# lipo_status.net
KiCad netlist of a schematic drawn in EAGLE
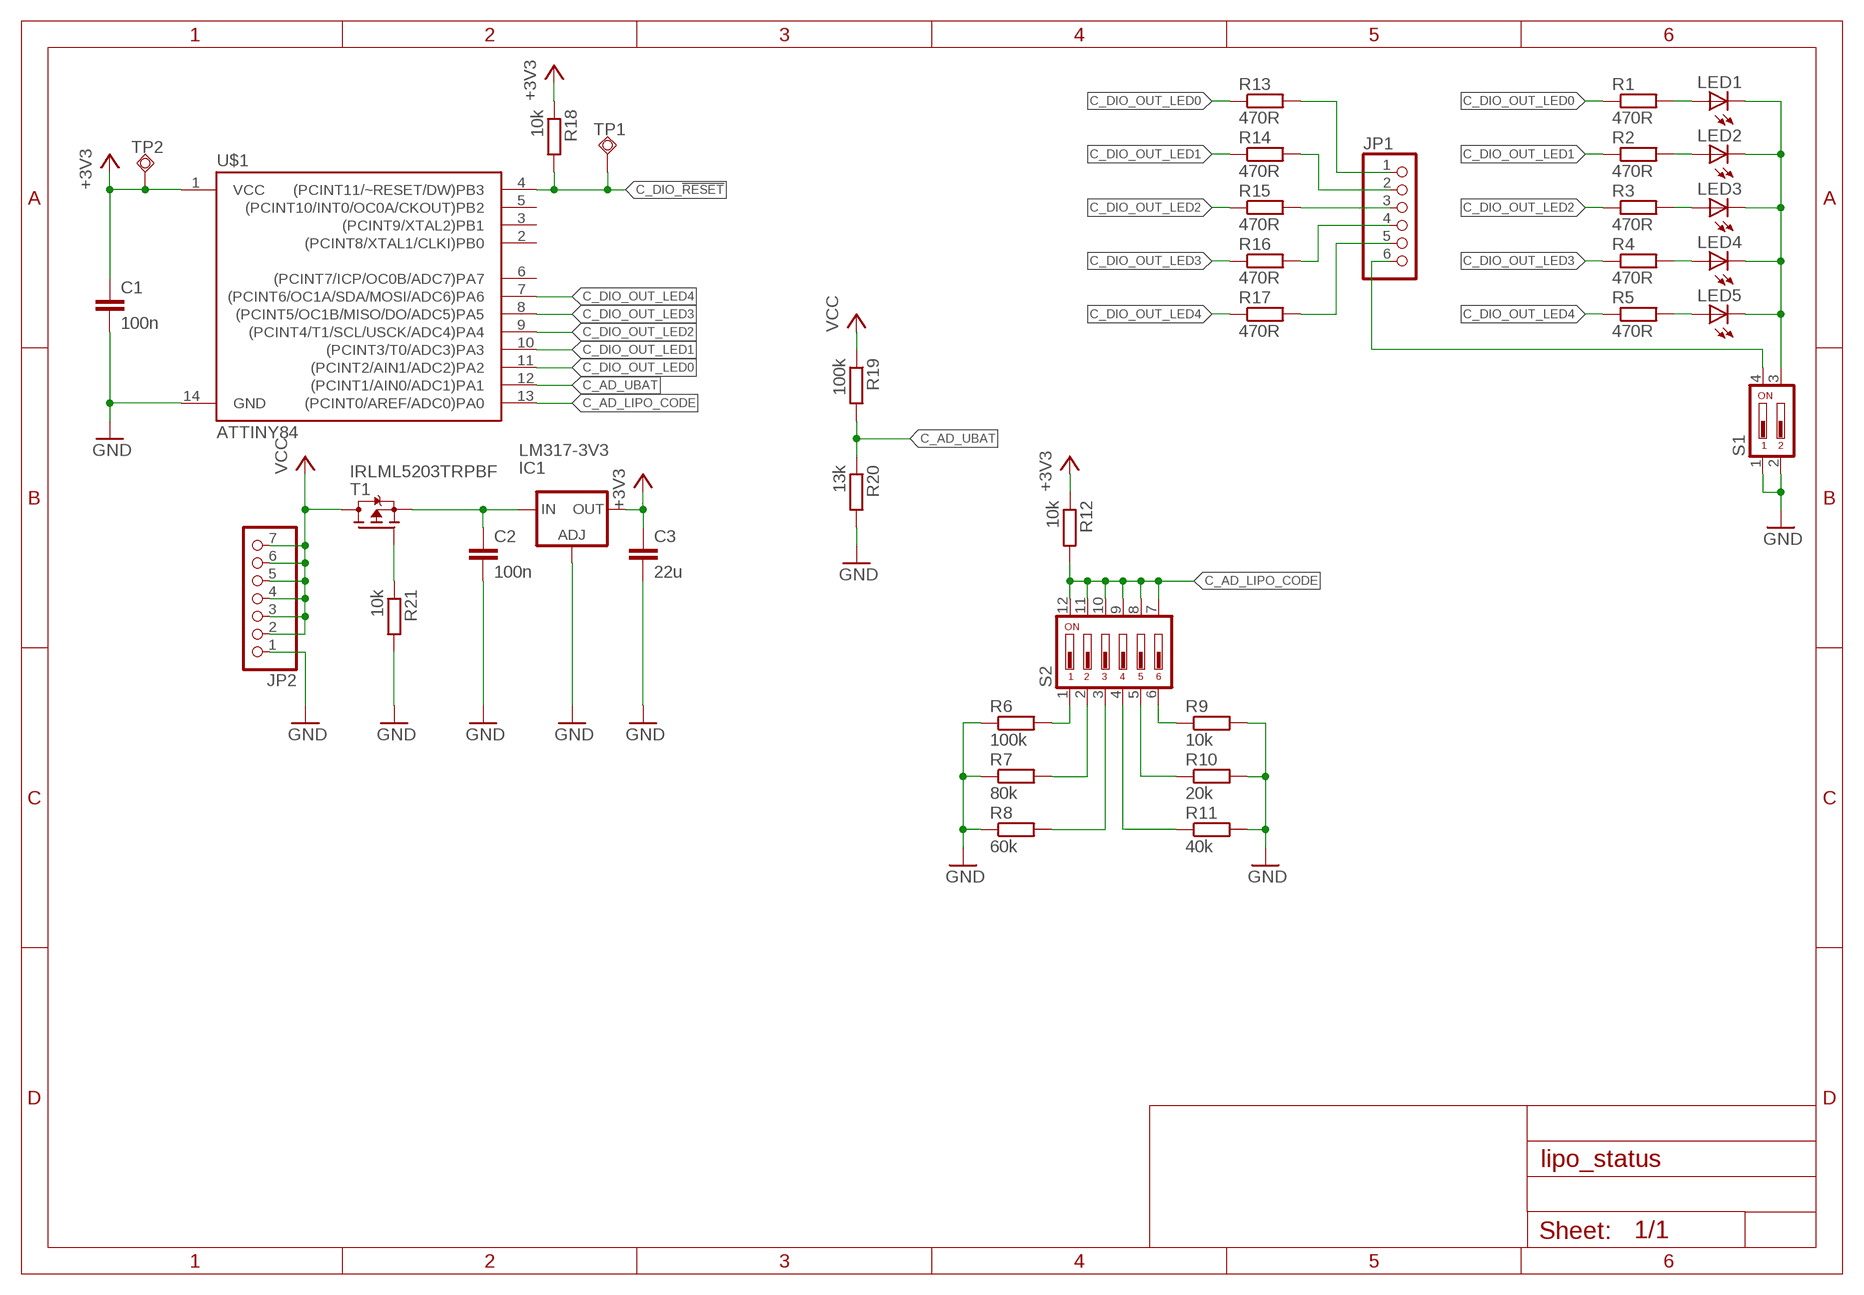
[diagram p0: schematic, sheet 1]

(export (version "E")
  (design (tool "Eeschema 10.0.6"))
  (components
    (comp (ref "C1")
      (value "100n")
      (footprint "eagle-import:C0603")
      (libsource (lib "eagle-import") (part "C-EUC0603"))
    )
    (comp (ref "C2")
      (value "100n")
      (footprint "eagle-import:C0805")
      (libsource (lib "eagle-import") (part "C-EUC0805"))
    )
    (comp (ref "C3")
      (value "22u")
      (footprint "eagle-import:C0805")
      (libsource (lib "eagle-import") (part "C-EUC0805"))
    )
    (comp (ref "IC1")
      (value "LM317-3V3")
      (footprint "eagle-import:SOT223")
      (libsource (lib "eagle-import") (part "LM317?MBSTT3"))
    )
    (comp (ref "JP1")
      (value "PINHD-1X6")
      (footprint "eagle-import:1X06")
      (libsource (lib "eagle-import") (part "PINHD-1X6"))
    )
    (comp (ref "JP2")
      (value "PINHD-1X7")
      (footprint "eagle-import:1X07")
      (libsource (lib "eagle-import") (part "PINHD-1X7"))
    )
    (comp (ref "LED1")
      (value "LEDCHIP-LED0805")
      (footprint "eagle-import:CHIP-LED0805")
      (libsource (lib "eagle-import") (part "LEDCHIP-LED0805"))
    )
    (comp (ref "LED2")
      (value "LEDCHIP-LED0805")
      (footprint "eagle-import:CHIP-LED0805")
      (libsource (lib "eagle-import") (part "LEDCHIP-LED0805"))
    )
    (comp (ref "LED3")
      (value "LEDCHIP-LED0805")
      (footprint "eagle-import:CHIP-LED0805")
      (libsource (lib "eagle-import") (part "LEDCHIP-LED0805"))
    )
    (comp (ref "LED4")
      (value "LEDCHIP-LED0805")
      (footprint "eagle-import:CHIP-LED0805")
      (libsource (lib "eagle-import") (part "LEDCHIP-LED0805"))
    )
    (comp (ref "LED5")
      (value "LEDCHIP-LED0805")
      (footprint "eagle-import:CHIP-LED0805")
      (libsource (lib "eagle-import") (part "LEDCHIP-LED0805"))
    )
    (comp (ref "R1")
      (value "470R")
      (footprint "eagle-import:R0603")
      (libsource (lib "eagle-import") (part "R-EU_R0603"))
    )
    (comp (ref "R2")
      (value "470R")
      (footprint "eagle-import:R0603")
      (libsource (lib "eagle-import") (part "R-EU_R0603"))
    )
    (comp (ref "R3")
      (value "470R")
      (footprint "eagle-import:R0603")
      (libsource (lib "eagle-import") (part "R-EU_R0603"))
    )
    (comp (ref "R4")
      (value "470R")
      (footprint "eagle-import:R0603")
      (libsource (lib "eagle-import") (part "R-EU_R0603"))
    )
    (comp (ref "R5")
      (value "470R")
      (footprint "eagle-import:R0603")
      (libsource (lib "eagle-import") (part "R-EU_R0603"))
    )
    (comp (ref "R6")
      (value "100k")
      (footprint "eagle-import:R0603")
      (libsource (lib "eagle-import") (part "R-EU_R0603"))
    )
    (comp (ref "R7")
      (value "80k")
      (footprint "eagle-import:R0603")
      (libsource (lib "eagle-import") (part "R-EU_R0603"))
    )
    (comp (ref "R8")
      (value "60k")
      (footprint "eagle-import:R0603")
      (libsource (lib "eagle-import") (part "R-EU_R0603"))
    )
    (comp (ref "R9")
      (value "10k")
      (footprint "eagle-import:R0603")
      (libsource (lib "eagle-import") (part "R-EU_R0603"))
    )
    (comp (ref "R10")
      (value "20k")
      (footprint "eagle-import:R0603")
      (libsource (lib "eagle-import") (part "R-EU_R0603"))
    )
    (comp (ref "R11")
      (value "40k")
      (footprint "eagle-import:R0603")
      (libsource (lib "eagle-import") (part "R-EU_R0603"))
    )
    (comp (ref "R12")
      (value "10k")
      (footprint "eagle-import:R0603")
      (libsource (lib "eagle-import") (part "R-EU_R0603"))
    )
    (comp (ref "R13")
      (value "470R")
      (footprint "eagle-import:R0603")
      (libsource (lib "eagle-import") (part "R-EU_R0603"))
    )
    (comp (ref "R14")
      (value "470R")
      (footprint "eagle-import:R0603")
      (libsource (lib "eagle-import") (part "R-EU_R0603"))
    )
    (comp (ref "R15")
      (value "470R")
      (footprint "eagle-import:R0603")
      (libsource (lib "eagle-import") (part "R-EU_R0603"))
    )
    (comp (ref "R16")
      (value "470R")
      (footprint "eagle-import:R0603")
      (libsource (lib "eagle-import") (part "R-EU_R0603"))
    )
    (comp (ref "R17")
      (value "470R")
      (footprint "eagle-import:R0603")
      (libsource (lib "eagle-import") (part "R-EU_R0603"))
    )
    (comp (ref "R18")
      (value "10k")
      (footprint "eagle-import:R0603")
      (libsource (lib "eagle-import") (part "R-EU_R0603"))
    )
    (comp (ref "R19")
      (value "100k")
      (footprint "eagle-import:R0603")
      (libsource (lib "eagle-import") (part "R-EU_R0603"))
    )
    (comp (ref "R20")
      (value "13k")
      (footprint "eagle-import:R0603")
      (libsource (lib "eagle-import") (part "R-EU_R0603"))
    )
    (comp (ref "R21")
      (value "10k")
      (footprint "eagle-import:R0603")
      (libsource (lib "eagle-import") (part "R-EU_R0603"))
    )
    (comp (ref "S1")
      (value "DIP02YL")
      (footprint "eagle-import:DIP02YL")
      (libsource (lib "eagle-import") (part "DIP02YL"))
    )
    (comp (ref "S2")
      (value "DIP06YL")
      (footprint "eagle-import:DIP06YL")
      (libsource (lib "eagle-import") (part "DIP06YL"))
    )
    (comp (ref "T1")
      (value "IRLML5203TRPBF")
      (footprint "eagle-import:SOT23")
      (libsource (lib "eagle-import") (part "IRLML5203TRPBF"))
    )
    (comp (ref "TP1")
      (value "TPSQPAD1-13")
      (footprint "eagle-import:P1-13")
      (libsource (lib "eagle-import") (part "TPSQPAD1-13"))
    )
    (comp (ref "TP2")
      (value "TPSQPAD1-13")
      (footprint "eagle-import:P1-13")
      (libsource (lib "eagle-import") (part "TPSQPAD1-13"))
    )
    (comp (ref "U$1")
      (value "ATTINY84")
      (footprint "eagle-import:SO14")
      (libsource (lib "eagle-import") (part "ATTINY84"))
    )
  )
  (nets
    (net (code "1") (name "+3V3") (class "Default")
      (node (ref "C1") (pin "1") (pinfunction "1_1") (pintype "passive"))
      (node (ref "C3") (pin "1") (pinfunction "1_1") (pintype "passive"))
      (node (ref "IC1") (pin "4") (pinfunction "OUT_4") (pintype "passive"))
      (node (ref "R12") (pin "1") (pinfunction "1_1") (pintype "passive"))
      (node (ref "R18") (pin "1") (pinfunction "1_1") (pintype "passive"))
      (node (ref "TP2") (pin "TP") (pinfunction "TP_TP") (pintype "input"))
      (node (ref "U$1") (pin "1") (pinfunction "VCC_1") (pintype "bidirectional"))
    )
    (net (code "2") (name "/C_DIO_~{RESET}") (class "Default")
      (node (ref "R18") (pin "2") (pinfunction "2_2") (pintype "passive"))
      (node (ref "TP1") (pin "TP") (pinfunction "TP_TP") (pintype "input"))
      (node (ref "U$1") (pin "4") (pinfunction "(PCINT11/~{RESET/DW})PB3_4") (pintype "bidirectional"))
    )
    (net (code "3") (name "C_AD_LIPO_CODE") (class "Default")
      (node (ref "R12") (pin "2") (pinfunction "2_2") (pintype "passive"))
      (node (ref "S2") (pin "10") (pinfunction "10_10") (pintype "passive"))
      (node (ref "S2") (pin "11") (pinfunction "11_11") (pintype "passive"))
      (node (ref "S2") (pin "12") (pinfunction "12_12") (pintype "passive"))
      (node (ref "S2") (pin "7") (pinfunction "7_7") (pintype "passive"))
      (node (ref "S2") (pin "8") (pinfunction "8_8") (pintype "passive"))
      (node (ref "S2") (pin "9") (pinfunction "9_9") (pintype "passive"))
      (node (ref "U$1") (pin "13") (pinfunction "(PCINT0/AREF/ADC0)PA0_13") (pintype "bidirectional"))
    )
    (net (code "4") (name "C_AD_UBAT") (class "Default")
      (node (ref "R19") (pin "2") (pinfunction "2_2") (pintype "passive"))
      (node (ref "R20") (pin "1") (pinfunction "1_1") (pintype "passive"))
      (node (ref "U$1") (pin "12") (pinfunction "(PCINT1/AIN0/ADC1)PA1_12") (pintype "bidirectional"))
    )
    (net (code "5") (name "C_DIO_OUT_LED0") (class "Default")
      (node (ref "R1") (pin "1") (pinfunction "1_1") (pintype "passive"))
      (node (ref "R13") (pin "1") (pinfunction "1_1") (pintype "passive"))
      (node (ref "U$1") (pin "11") (pinfunction "(PCINT2/AIN1/ADC2)PA2_11") (pintype "bidirectional"))
    )
    (net (code "6") (name "C_DIO_OUT_LED1") (class "Default")
      (node (ref "R14") (pin "1") (pinfunction "1_1") (pintype "passive"))
      (node (ref "R2") (pin "1") (pinfunction "1_1") (pintype "passive"))
      (node (ref "U$1") (pin "10") (pinfunction "(PCINT3/T0/ADC3)PA3_10") (pintype "bidirectional"))
    )
    (net (code "7") (name "C_DIO_OUT_LED2") (class "Default")
      (node (ref "R15") (pin "1") (pinfunction "1_1") (pintype "passive"))
      (node (ref "R3") (pin "1") (pinfunction "1_1") (pintype "passive"))
      (node (ref "U$1") (pin "9") (pinfunction "(PCINT4/T1/SCL/USCK/ADC4)PA4_9") (pintype "bidirectional"))
    )
    (net (code "8") (name "C_DIO_OUT_LED3") (class "Default")
      (node (ref "R16") (pin "1") (pinfunction "1_1") (pintype "passive"))
      (node (ref "R4") (pin "1") (pinfunction "1_1") (pintype "passive"))
      (node (ref "U$1") (pin "8") (pinfunction "(PCINT5/OC1B/MISO/DO/ADC5)PA5_8") (pintype "bidirectional"))
    )
    (net (code "9") (name "C_DIO_OUT_LED4") (class "Default")
      (node (ref "R17") (pin "1") (pinfunction "1_1") (pintype "passive"))
      (node (ref "R5") (pin "1") (pinfunction "1_1") (pintype "passive"))
      (node (ref "U$1") (pin "7") (pinfunction "(PCINT6/OC1A/SDA/MOSI/ADC6)PA6_7") (pintype "bidirectional"))
    )
    (net (code "10") (name "GND") (class "Default")
      (node (ref "C1") (pin "2") (pinfunction "2_2") (pintype "passive"))
      (node (ref "C2") (pin "2") (pinfunction "2_2") (pintype "passive"))
      (node (ref "C3") (pin "2") (pinfunction "2_2") (pintype "passive"))
      (node (ref "IC1") (pin "1") (pinfunction "ADJ_1") (pintype "input"))
      (node (ref "JP2") (pin "1") (pinfunction "1_1") (pintype "passive"))
      (node (ref "R10") (pin "2") (pinfunction "2_2") (pintype "passive"))
      (node (ref "R11") (pin "2") (pinfunction "2_2") (pintype "passive"))
      (node (ref "R20") (pin "2") (pinfunction "2_2") (pintype "passive"))
      (node (ref "R21") (pin "2") (pinfunction "2_2") (pintype "passive"))
      (node (ref "R6") (pin "1") (pinfunction "1_1") (pintype "passive"))
      (node (ref "R7") (pin "1") (pinfunction "1_1") (pintype "passive"))
      (node (ref "R8") (pin "1") (pinfunction "1_1") (pintype "passive"))
      (node (ref "R9") (pin "2") (pinfunction "2_2") (pintype "passive"))
      (node (ref "S1") (pin "1") (pinfunction "1_1") (pintype "passive"))
      (node (ref "S1") (pin "2") (pinfunction "2_2") (pintype "passive"))
      (node (ref "U$1") (pin "14") (pinfunction "GND_14") (pintype "bidirectional"))
    )
    (net (code "11") (name "Net-(IC1-IN)") (class "Default")
      (node (ref "C2") (pin "1") (pinfunction "1_1") (pintype "passive"))
      (node (ref "IC1") (pin "3") (pinfunction "IN_3") (pintype "input"))
      (node (ref "T1") (pin "2") (pinfunction "S_2") (pintype "passive"))
    )
    (net (code "12") (name "Net-(JP1-Pad1)") (class "Default")
      (node (ref "JP1") (pin "1") (pinfunction "1_1") (pintype "passive"))
      (node (ref "R13") (pin "2") (pinfunction "2_2") (pintype "passive"))
    )
    (net (code "13") (name "Net-(JP1-Pad2)") (class "Default")
      (node (ref "JP1") (pin "2") (pinfunction "2_2") (pintype "passive"))
      (node (ref "R14") (pin "2") (pinfunction "2_2") (pintype "passive"))
    )
    (net (code "14") (name "Net-(JP1-Pad3)") (class "Default")
      (node (ref "JP1") (pin "3") (pinfunction "3_3") (pintype "passive"))
      (node (ref "R15") (pin "2") (pinfunction "2_2") (pintype "passive"))
    )
    (net (code "15") (name "Net-(JP1-Pad4)") (class "Default")
      (node (ref "JP1") (pin "4") (pinfunction "4_4") (pintype "passive"))
      (node (ref "R16") (pin "2") (pinfunction "2_2") (pintype "passive"))
    )
    (net (code "16") (name "Net-(JP1-Pad5)") (class "Default")
      (node (ref "JP1") (pin "5") (pinfunction "5_5") (pintype "passive"))
      (node (ref "R17") (pin "2") (pinfunction "2_2") (pintype "passive"))
    )
    (net (code "17") (name "Net-(JP1-Pad6)") (class "Default")
      (node (ref "JP1") (pin "6") (pinfunction "6_6") (pintype "passive"))
      (node (ref "S1") (pin "4") (pinfunction "4_4") (pintype "passive"))
    )
    (net (code "18") (name "Net-(LED1-PadA)") (class "Default")
      (node (ref "LED1") (pin "A") (pinfunction "A_A") (pintype "passive"))
      (node (ref "R1") (pin "2") (pinfunction "2_2") (pintype "passive"))
    )
    (net (code "19") (name "Net-(LED1-PadC)") (class "Default")
      (node (ref "LED1") (pin "C") (pinfunction "C_C") (pintype "passive"))
      (node (ref "LED2") (pin "C") (pinfunction "C_C") (pintype "passive"))
      (node (ref "LED3") (pin "C") (pinfunction "C_C") (pintype "passive"))
      (node (ref "LED4") (pin "C") (pinfunction "C_C") (pintype "passive"))
      (node (ref "LED5") (pin "C") (pinfunction "C_C") (pintype "passive"))
      (node (ref "S1") (pin "3") (pinfunction "3_3") (pintype "passive"))
    )
    (net (code "20") (name "Net-(LED2-PadA)") (class "Default")
      (node (ref "LED2") (pin "A") (pinfunction "A_A") (pintype "passive"))
      (node (ref "R2") (pin "2") (pinfunction "2_2") (pintype "passive"))
    )
    (net (code "21") (name "Net-(LED3-PadA)") (class "Default")
      (node (ref "LED3") (pin "A") (pinfunction "A_A") (pintype "passive"))
      (node (ref "R3") (pin "2") (pinfunction "2_2") (pintype "passive"))
    )
    (net (code "22") (name "Net-(LED4-PadA)") (class "Default")
      (node (ref "LED4") (pin "A") (pinfunction "A_A") (pintype "passive"))
      (node (ref "R4") (pin "2") (pinfunction "2_2") (pintype "passive"))
    )
    (net (code "23") (name "Net-(LED5-PadA)") (class "Default")
      (node (ref "LED5") (pin "A") (pinfunction "A_A") (pintype "passive"))
      (node (ref "R5") (pin "2") (pinfunction "2_2") (pintype "passive"))
    )
    (net (code "24") (name "Net-(R6-Pad2)") (class "Default")
      (node (ref "R6") (pin "2") (pinfunction "2_2") (pintype "passive"))
      (node (ref "S2") (pin "1") (pinfunction "1_1") (pintype "passive"))
    )
    (net (code "25") (name "Net-(R7-Pad2)") (class "Default")
      (node (ref "R7") (pin "2") (pinfunction "2_2") (pintype "passive"))
      (node (ref "S2") (pin "2") (pinfunction "2_2") (pintype "passive"))
    )
    (net (code "26") (name "Net-(R8-Pad2)") (class "Default")
      (node (ref "R8") (pin "2") (pinfunction "2_2") (pintype "passive"))
      (node (ref "S2") (pin "3") (pinfunction "3_3") (pintype "passive"))
    )
    (net (code "27") (name "Net-(R9-Pad1)") (class "Default")
      (node (ref "R9") (pin "1") (pinfunction "1_1") (pintype "passive"))
      (node (ref "S2") (pin "6") (pinfunction "6_6") (pintype "passive"))
    )
    (net (code "28") (name "Net-(R10-Pad1)") (class "Default")
      (node (ref "R10") (pin "1") (pinfunction "1_1") (pintype "passive"))
      (node (ref "S2") (pin "5") (pinfunction "5_5") (pintype "passive"))
    )
    (net (code "29") (name "Net-(R11-Pad1)") (class "Default")
      (node (ref "R11") (pin "1") (pinfunction "1_1") (pintype "passive"))
      (node (ref "S2") (pin "4") (pinfunction "4_4") (pintype "passive"))
    )
    (net (code "30") (name "Net-(T1-G)") (class "Default")
      (node (ref "R21") (pin "1") (pinfunction "1_1") (pintype "passive"))
      (node (ref "T1") (pin "1") (pinfunction "G_1") (pintype "passive"))
    )
    (net (code "31") (name "VCC") (class "Default")
      (node (ref "JP2") (pin "2") (pinfunction "2_2") (pintype "passive"))
      (node (ref "JP2") (pin "3") (pinfunction "3_3") (pintype "passive"))
      (node (ref "JP2") (pin "4") (pinfunction "4_4") (pintype "passive"))
      (node (ref "JP2") (pin "5") (pinfunction "5_5") (pintype "passive"))
      (node (ref "JP2") (pin "6") (pinfunction "6_6") (pintype "passive"))
      (node (ref "JP2") (pin "7") (pinfunction "7_7") (pintype "passive"))
      (node (ref "R19") (pin "1") (pinfunction "1_1") (pintype "passive"))
      (node (ref "T1") (pin "3") (pinfunction "D_3") (pintype "passive"))
    )
    (net (code "32") (name "unconnected-(U$1-(PCINT7{slash}ICP{slash}OC0B{slash}ADC7)PA7-Pad6)") (class "Default")
      (node (ref "U$1") (pin "6") (pinfunction "(PCINT7/ICP/OC0B/ADC7)PA7_6") (pintype "bidirectional"))
    )
    (net (code "33") (name "unconnected-(U$1-(PCINT8{slash}XTAL1{slash}CLKI)PB0-Pad2)") (class "Default")
      (node (ref "U$1") (pin "2") (pinfunction "(PCINT8/XTAL1/CLKI)PB0_2") (pintype "bidirectional"))
    )
    (net (code "34") (name "unconnected-(U$1-(PCINT9{slash}XTAL2)PB1-Pad3)") (class "Default")
      (node (ref "U$1") (pin "3") (pinfunction "(PCINT9/XTAL2)PB1_3") (pintype "bidirectional"))
    )
    (net (code "35") (name "unconnected-(U$1-(PCINT10{slash}INT0{slash}OC0A{slash}CKOUT)PB2-Pad5)") (class "Default")
      (node (ref "U$1") (pin "5") (pinfunction "(PCINT10/INT0/OC0A/CKOUT)PB2_5") (pintype "bidirectional"))
    )
  )
)
